# ECG.net
KiCad netlist of a schematic drawn in EAGLE
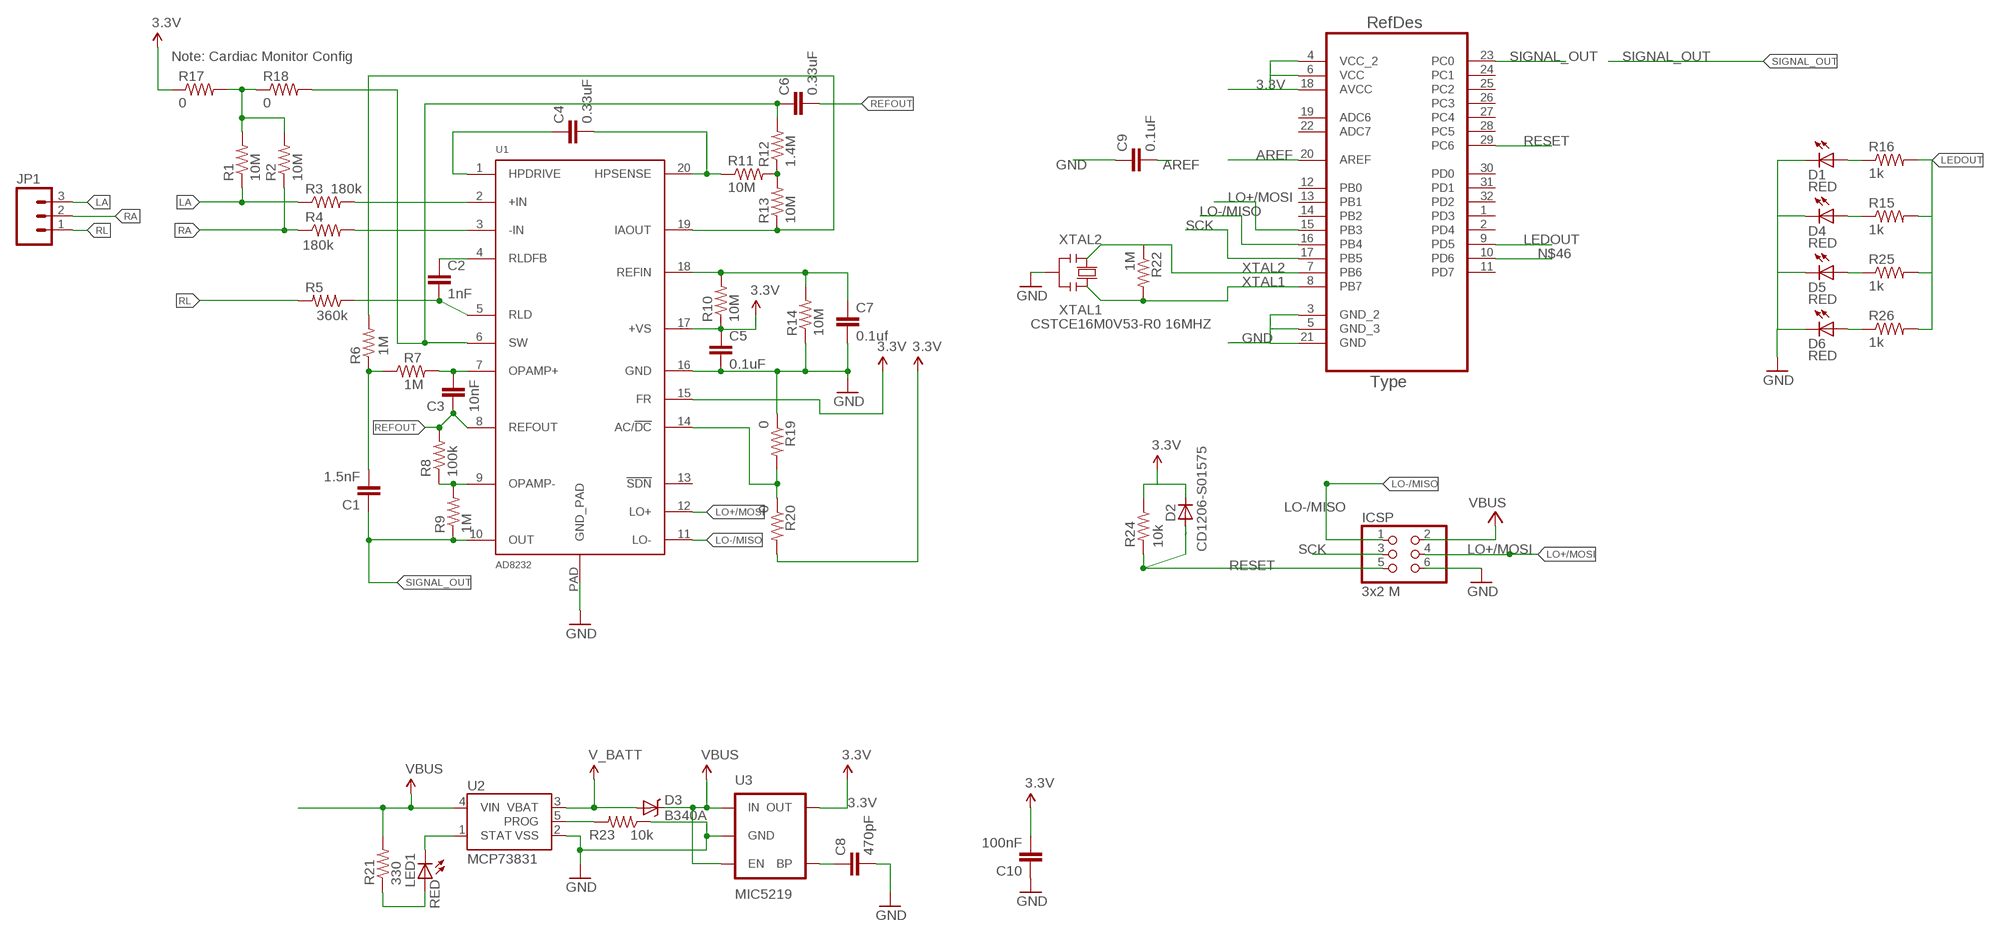
[diagram p0: schematic, sheet 1]

(export (version "E")
  (design (tool "Eeschema 10.0.6"))
  (components
    (comp (ref "C1")
      (value "1.5nF")
      (footprint "eagle-import:0402-CAP")
      (libsource (lib "eagle-import") (part "CAP0402-CAP"))
    )
    (comp (ref "C2")
      (value "1nF")
      (footprint "eagle-import:0402-CAP")
      (libsource (lib "eagle-import") (part "CAP0402-CAP"))
    )
    (comp (ref "C3")
      (value "10nF")
      (footprint "eagle-import:0402-CAP")
      (libsource (lib "eagle-import") (part "CAP0402-CAP"))
    )
    (comp (ref "C4")
      (value "0.33uF")
      (footprint "eagle-import:0805")
      (libsource (lib "eagle-import") (part "CAP0805"))
    )
    (comp (ref "C5")
      (value "0.1uF")
      (footprint "eagle-import:0402-CAP")
      (libsource (lib "eagle-import") (part "CAP0402-CAP"))
    )
    (comp (ref "C6")
      (value "0.33uF")
      (footprint "eagle-import:0805")
      (libsource (lib "eagle-import") (part "CAP0805"))
    )
    (comp (ref "C7")
      (value "0.1uf")
      (footprint "eagle-import:0402-CAP")
      (libsource (lib "eagle-import") (part "CAP0402-CAP"))
    )
    (comp (ref "C8")
      (value "470pF")
      (footprint "eagle-import:0603-CAP")
      (libsource (lib "eagle-import") (part "CAP0603-CAP"))
    )
    (comp (ref "C9")
      (value "0.1uF")
      (footprint "eagle-import:0402-CAP")
      (libsource (lib "eagle-import") (part "CAP0402-CAP"))
    )
    (comp (ref "C10")
      (value "100nF")
      (footprint "eagle-import:0402-CAP")
      (libsource (lib "eagle-import") (part "CAP0402-CAP"))
    )
    (comp (ref "D1")
      (value "RED")
      (footprint "eagle-import:LED-0603@1")
      (libsource (lib "eagle-import") (part "LED-RED0603"))
    )
    (comp (ref "D2")
      (value "CD1206-S01575")
      (footprint "eagle-import:MINIMELF")
      (libsource (lib "eagle-import") (part "DIODE-MINIMELF"))
    )
    (comp (ref "D3")
      (value "B340A")
      (footprint "eagle-import:SMA-DIODE")
      (libsource (lib "eagle-import") (part "DIODE-SCHOTTKY-B340A"))
    )
    (comp (ref "D4")
      (value "RED")
      (footprint "eagle-import:LED-0603@1")
      (libsource (lib "eagle-import") (part "LED-RED0603"))
    )
    (comp (ref "D5")
      (value "RED")
      (footprint "eagle-import:LED-0603@1")
      (libsource (lib "eagle-import") (part "LED-RED0603"))
    )
    (comp (ref "D6")
      (value "RED")
      (footprint "eagle-import:LED-0603@1")
      (libsource (lib "eagle-import") (part "LED-RED0603"))
    )
    (comp (ref "ICSP")
      (value "3x2 M")
      (footprint "eagle-import:2X03")
      (libsource (lib "eagle-import") (part "PINHD-2X3"))
    )
    (comp (ref "JP1")
      (value "M03PTH")
      (footprint "eagle-import:1X03")
      (libsource (lib "eagle-import") (part "M03PTH"))
    )
    (comp (ref "LED1")
      (value "RED")
      (footprint "eagle-import:LED-0603")
      (libsource (lib "eagle-import") (part "LED0603"))
    )
    (comp (ref "R1")
      (value "10M")
      (footprint "eagle-import:0402-RES")
      (libsource (lib "eagle-import") (part "RESISTOR0402-RES"))
    )
    (comp (ref "R2")
      (value "10M")
      (footprint "eagle-import:0402-RES")
      (libsource (lib "eagle-import") (part "RESISTOR0402-RES"))
    )
    (comp (ref "R3")
      (value "180k")
      (footprint "eagle-import:0402-RES")
      (libsource (lib "eagle-import") (part "RESISTOR0402-RES"))
    )
    (comp (ref "R4")
      (value "180k")
      (footprint "eagle-import:0402-RES")
      (libsource (lib "eagle-import") (part "RESISTOR0402-RES"))
    )
    (comp (ref "R5")
      (value "360k")
      (footprint "eagle-import:0402-RES")
      (libsource (lib "eagle-import") (part "RESISTOR0402-RES"))
    )
    (comp (ref "R6")
      (value "1M")
      (footprint "eagle-import:0402-RES")
      (libsource (lib "eagle-import") (part "RESISTOR0402-RES"))
    )
    (comp (ref "R7")
      (value "1M")
      (footprint "eagle-import:0402-RES")
      (libsource (lib "eagle-import") (part "RESISTOR0402-RES"))
    )
    (comp (ref "R8")
      (value "100k")
      (footprint "eagle-import:0402-RES")
      (libsource (lib "eagle-import") (part "RESISTOR0402-RES"))
    )
    (comp (ref "R9")
      (value "1M")
      (footprint "eagle-import:0402-RES")
      (libsource (lib "eagle-import") (part "RESISTOR0402-RES"))
    )
    (comp (ref "R10")
      (value "10M")
      (footprint "eagle-import:0402-RES")
      (libsource (lib "eagle-import") (part "RESISTOR0402-RES"))
    )
    (comp (ref "R11")
      (value "10M")
      (footprint "eagle-import:0402-RES")
      (libsource (lib "eagle-import") (part "RESISTOR0402-RES"))
    )
    (comp (ref "R12")
      (value "1.4M")
      (footprint "eagle-import:0402-RES")
      (libsource (lib "eagle-import") (part "RESISTOR0402-RES"))
    )
    (comp (ref "R13")
      (value "10M")
      (footprint "eagle-import:0402-RES")
      (libsource (lib "eagle-import") (part "RESISTOR0402-RES"))
    )
    (comp (ref "R14")
      (value "10M")
      (footprint "eagle-import:0402-RES")
      (libsource (lib "eagle-import") (part "RESISTOR0402-RES"))
    )
    (comp (ref "R15")
      (value "1k")
      (footprint "eagle-import:0603-RES@1")
      (libsource (lib "eagle-import") (part "1K-1%"))
    )
    (comp (ref "R16")
      (value "1k")
      (footprint "eagle-import:0603-RES@1")
      (libsource (lib "eagle-import") (part "1K-1%"))
    )
    (comp (ref "R17")
      (value "0")
      (footprint "eagle-import:0603")
      (libsource (lib "eagle-import") (part "0OHM1/10W5%(0603)"))
    )
    (comp (ref "R18")
      (value "0")
      (footprint "eagle-import:0603")
      (libsource (lib "eagle-import") (part "0OHM1/10W5%(0603)"))
    )
    (comp (ref "R19")
      (value "0")
      (footprint "eagle-import:0603")
      (libsource (lib "eagle-import") (part "0OHM1/10W5%(0603)"))
    )
    (comp (ref "R20")
      (value "0")
      (footprint "eagle-import:0603")
      (libsource (lib "eagle-import") (part "0OHM1/10W5%(0603)"))
    )
    (comp (ref "R21")
      (value "330")
      (footprint "eagle-import:0603-RES")
      (libsource (lib "eagle-import") (part "RESISTOR0603-RES"))
    )
    (comp (ref "R22")
      (value "1M")
      (footprint "eagle-import:0402-RES")
      (libsource (lib "eagle-import") (part "RESISTOR0402-RES"))
    )
    (comp (ref "R23")
      (value "10k")
      (footprint "eagle-import:0603-RES")
      (libsource (lib "eagle-import") (part "SparkFun-Resistors_RESISTOR0603-RES"))
    )
    (comp (ref "R24")
      (value "10k")
      (footprint "eagle-import:0402-RES")
      (libsource (lib "eagle-import") (part "RESISTOR0402-RES"))
    )
    (comp (ref "R25")
      (value "1k")
      (footprint "eagle-import:0603-RES@1")
      (libsource (lib "eagle-import") (part "1K-1%"))
    )
    (comp (ref "R26")
      (value "1k")
      (footprint "eagle-import:0603-RES@1")
      (libsource (lib "eagle-import") (part "1K-1%"))
    )
    (comp (ref "U1")
      (value "AD8232")
      (footprint "eagle-import:LFCSP_20")
      (libsource (lib "eagle-import") (part "AD8232"))
    )
    (comp (ref "U2")
      (value "MCP73831")
      (footprint "eagle-import:SOT23-5")
      (fields (field (name "PROD_ID") "IC-09995"))
      (libsource (lib "eagle-import") (part "MCP73831"))
    )
    (comp (ref "U3")
      (value "MIC5219")
      (footprint "eagle-import:SOT23-5")
      (fields (field (name "PROD_ID") "VREG-09872"))
      (libsource (lib "eagle-import") (part "V_REG_MIC52193.3V"))
    )
    (comp (ref "U4")
      (value "ATMEGA328P-AU")
      (footprint "eagle-import:QFP80P900X900X120-32N")
      (libsource (lib "eagle-import") (part "ATMEGA328P-AU"))
    )
    (comp (ref "Y2")
      (value "CSTCE16M0V53-R0 16MHZ")
      (footprint "eagle-import:RESONATOR")
      (libsource (lib "eagle-import") (part "RESONATORMU"))
    )
  )
  (nets
    (net (code "1") (name "/AREF") (class "Default")
      (node (ref "C9") (pin "2") (pinfunction "2_2") (pintype "passive"))
      (node (ref "U4") (pin "20") (pinfunction "AREF_20") (pintype "input"))
    )
    (net (code "2") (name "/N$46") (class "Default")
      (node (ref "U4") (pin "10") (pinfunction "PD6_10") (pintype "bidirectional"))
    )
    (net (code "3") (name "/RESET") (class "Default")
      (node (ref "D2") (pin "A") (pinfunction "A_A") (pintype "passive"))
      (node (ref "ICSP") (pin "5") (pinfunction "5_5") (pintype "passive"))
      (node (ref "R24") (pin "2") (pinfunction "2_2") (pintype "passive"))
      (node (ref "U4") (pin "29") (pinfunction "PC6_29") (pintype "bidirectional"))
    )
    (net (code "4") (name "/SCK") (class "Default")
      (node (ref "ICSP") (pin "3") (pinfunction "3_3") (pintype "passive"))
      (node (ref "U4") (pin "17") (pinfunction "PB5_17") (pintype "bidirectional"))
    )
    (net (code "5") (name "/XTAL1") (class "Default")
      (node (ref "R22") (pin "2") (pinfunction "2_2") (pintype "passive"))
      (node (ref "U4") (pin "8") (pinfunction "PB7_8") (pintype "bidirectional"))
      (node (ref "Y2") (pin "3") (pinfunction "3_3") (pintype "passive"))
    )
    (net (code "6") (name "/XTAL2") (class "Default")
      (node (ref "R22") (pin "1") (pinfunction "1_1") (pintype "passive"))
      (node (ref "U4") (pin "7") (pinfunction "PB6_7") (pintype "bidirectional"))
      (node (ref "Y2") (pin "1") (pinfunction "1_1") (pintype "passive"))
    )
    (net (code "7") (name "3.3V") (class "Default")
      (node (ref "C10") (pin "2") (pinfunction "2_2") (pintype "passive"))
      (node (ref "C5") (pin "1") (pinfunction "1_1") (pintype "passive"))
      (node (ref "D2") (pin "C") (pinfunction "C_C") (pintype "passive"))
      (node (ref "R10") (pin "1") (pinfunction "1_1") (pintype "passive"))
      (node (ref "R17") (pin "1") (pinfunction "1_1") (pintype "passive"))
      (node (ref "R20") (pin "2") (pinfunction "2_2") (pintype "passive"))
      (node (ref "R24") (pin "1") (pinfunction "1_1") (pintype "passive"))
      (node (ref "U1") (pin "15") (pinfunction "FR_15") (pintype "bidirectional"))
      (node (ref "U1") (pin "17") (pinfunction "+VS_17") (pintype "bidirectional"))
      (node (ref "U3") (pin "5") (pinfunction "OUT_5") (pintype "passive"))
      (node (ref "U4") (pin "18") (pinfunction "AVCC_18") (pintype "power_in"))
      (node (ref "U4") (pin "4") (pinfunction "VCC_2_4") (pintype "power_in"))
      (node (ref "U4") (pin "6") (pinfunction "VCC_6") (pintype "power_in"))
    )
    (net (code "8") (name "GND") (class "Default")
      (node (ref "C10") (pin "1") (pinfunction "1_1") (pintype "passive"))
      (node (ref "C5") (pin "2") (pinfunction "2_2") (pintype "passive"))
      (node (ref "C7") (pin "2") (pinfunction "2_2") (pintype "passive"))
      (node (ref "C8") (pin "2") (pinfunction "2_2") (pintype "passive"))
      (node (ref "C9") (pin "1") (pinfunction "1_1") (pintype "passive"))
      (node (ref "D1") (pin "C") (pinfunction "C_C") (pintype "passive"))
      (node (ref "D4") (pin "C") (pinfunction "C_C") (pintype "passive"))
      (node (ref "D5") (pin "C") (pinfunction "C_C") (pintype "passive"))
      (node (ref "D6") (pin "C") (pinfunction "C_C") (pintype "passive"))
      (node (ref "ICSP") (pin "6") (pinfunction "6_6") (pintype "passive"))
      (node (ref "R14") (pin "1") (pinfunction "1_1") (pintype "passive"))
      (node (ref "R19") (pin "1") (pinfunction "1_1") (pintype "passive"))
      (node (ref "R23") (pin "1") (pinfunction "1_1") (pintype "passive"))
      (node (ref "U1") (pin "16") (pinfunction "GND_16") (pintype "bidirectional"))
      (node (ref "U1") (pin "PAD") (pinfunction "GND_PAD_PAD") (pintype "bidirectional"))
      (node (ref "U2") (pin "2") (pinfunction "VSS_2") (pintype "power_in"))
      (node (ref "U3") (pin "2") (pinfunction "GND_2") (pintype "input"))
      (node (ref "U4") (pin "21") (pinfunction "GND_21") (pintype "passive"))
      (node (ref "U4") (pin "3") (pinfunction "GND_2_3") (pintype "passive"))
      (node (ref "U4") (pin "5") (pinfunction "GND_3_5") (pintype "passive"))
      (node (ref "Y2") (pin "2") (pinfunction "2_2") (pintype "passive"))
    )
    (net (code "9") (name "LA") (class "Default")
      (node (ref "JP1") (pin "3") (pinfunction "3_3") (pintype "passive"))
      (node (ref "R1") (pin "1") (pinfunction "1_1") (pintype "passive"))
      (node (ref "R3") (pin "1") (pinfunction "1_1") (pintype "passive"))
    )
    (net (code "10") (name "LEDOUT") (class "Default")
      (node (ref "R15") (pin "2") (pinfunction "2_2") (pintype "passive"))
      (node (ref "R16") (pin "2") (pinfunction "2_2") (pintype "passive"))
      (node (ref "R25") (pin "2") (pinfunction "2_2") (pintype "passive"))
      (node (ref "R26") (pin "2") (pinfunction "2_2") (pintype "passive"))
      (node (ref "U4") (pin "9") (pinfunction "PD5_9") (pintype "bidirectional"))
    )
    (net (code "11") (name "LO+{slash}MOSI") (class "Default")
      (node (ref "ICSP") (pin "4") (pinfunction "4_4") (pintype "passive"))
      (node (ref "U1") (pin "12") (pinfunction "LO+_12") (pintype "bidirectional"))
      (node (ref "U4") (pin "15") (pinfunction "PB3_15") (pintype "bidirectional"))
    )
    (net (code "12") (name "LO-{slash}MISO") (class "Default")
      (node (ref "ICSP") (pin "1") (pinfunction "1_1") (pintype "passive"))
      (node (ref "U1") (pin "11") (pinfunction "LO-_11") (pintype "bidirectional"))
      (node (ref "U4") (pin "16") (pinfunction "PB4_16") (pintype "bidirectional"))
    )
    (net (code "13") (name "Net-(C1-Pad2)") (class "Default")
      (node (ref "C1") (pin "2") (pinfunction "2_2") (pintype "passive"))
      (node (ref "R6") (pin "1") (pinfunction "1_1") (pintype "passive"))
      (node (ref "R7") (pin "1") (pinfunction "1_1") (pintype "passive"))
    )
    (net (code "14") (name "Net-(D1-PadA)") (class "Default")
      (node (ref "D1") (pin "A") (pinfunction "A_A") (pintype "passive"))
      (node (ref "R16") (pin "1") (pinfunction "1_1") (pintype "passive"))
    )
    (net (code "15") (name "Net-(D4-PadA)") (class "Default")
      (node (ref "D4") (pin "A") (pinfunction "A_A") (pintype "passive"))
      (node (ref "R15") (pin "1") (pinfunction "1_1") (pintype "passive"))
    )
    (net (code "16") (name "Net-(D5-PadA)") (class "Default")
      (node (ref "D5") (pin "A") (pinfunction "A_A") (pintype "passive"))
      (node (ref "R25") (pin "1") (pinfunction "1_1") (pintype "passive"))
    )
    (net (code "17") (name "Net-(D6-PadA)") (class "Default")
      (node (ref "D6") (pin "A") (pinfunction "A_A") (pintype "passive"))
      (node (ref "R26") (pin "1") (pinfunction "1_1") (pintype "passive"))
    )
    (net (code "18") (name "Net-(LED1-PadA)") (class "Default")
      (node (ref "LED1") (pin "A") (pinfunction "A_A") (pintype "passive"))
      (node (ref "R21") (pin "1") (pinfunction "1_1") (pintype "passive"))
    )
    (net (code "19") (name "Net-(R1-Pad2)") (class "Default")
      (node (ref "R1") (pin "2") (pinfunction "2_2") (pintype "passive"))
      (node (ref "R17") (pin "2") (pinfunction "2_2") (pintype "passive"))
      (node (ref "R18") (pin "1") (pinfunction "1_1") (pintype "passive"))
      (node (ref "R2") (pin "2") (pinfunction "2_2") (pintype "passive"))
    )
    (net (code "20") (name "Net-(R11-Pad2)") (class "Default")
      (node (ref "R11") (pin "2") (pinfunction "2_2") (pintype "passive"))
      (node (ref "R12") (pin "1") (pinfunction "1_1") (pintype "passive"))
      (node (ref "R13") (pin "2") (pinfunction "2_2") (pintype "passive"))
    )
    (net (code "21") (name "Net-(U1-+IN)") (class "Default")
      (node (ref "R3") (pin "2") (pinfunction "2_2") (pintype "passive"))
      (node (ref "U1") (pin "2") (pinfunction "+IN_2") (pintype "bidirectional"))
    )
    (net (code "22") (name "Net-(U1--IN)") (class "Default")
      (node (ref "R4") (pin "2") (pinfunction "2_2") (pintype "passive"))
      (node (ref "U1") (pin "3") (pinfunction "-IN_3") (pintype "bidirectional"))
    )
    (net (code "23") (name "Net-(U1-AC{slash}~{DC})") (class "Default")
      (node (ref "R19") (pin "2") (pinfunction "2_2") (pintype "passive"))
      (node (ref "R20") (pin "1") (pinfunction "1_1") (pintype "passive"))
      (node (ref "U1") (pin "14") (pinfunction "AC/~{DC}_14") (pintype "bidirectional"))
    )
    (net (code "24") (name "Net-(U1-HPDRIVE)") (class "Default")
      (node (ref "C4") (pin "1") (pinfunction "1_1") (pintype "passive"))
      (node (ref "U1") (pin "1") (pinfunction "HPDRIVE_1") (pintype "bidirectional"))
    )
    (net (code "25") (name "Net-(U1-HPSENSE)") (class "Default")
      (node (ref "C4") (pin "2") (pinfunction "2_2") (pintype "passive"))
      (node (ref "R11") (pin "1") (pinfunction "1_1") (pintype "passive"))
      (node (ref "U1") (pin "20") (pinfunction "HPSENSE_20") (pintype "bidirectional"))
    )
    (net (code "26") (name "Net-(U1-IAOUT)") (class "Default")
      (node (ref "R13") (pin "1") (pinfunction "1_1") (pintype "passive"))
      (node (ref "R6") (pin "2") (pinfunction "2_2") (pintype "passive"))
      (node (ref "U1") (pin "19") (pinfunction "IAOUT_19") (pintype "bidirectional"))
    )
    (net (code "27") (name "Net-(U1-OPAMP+)") (class "Default")
      (node (ref "C3") (pin "2") (pinfunction "2_2") (pintype "passive"))
      (node (ref "R7") (pin "2") (pinfunction "2_2") (pintype "passive"))
      (node (ref "U1") (pin "7") (pinfunction "OPAMP+_7") (pintype "bidirectional"))
    )
    (net (code "28") (name "Net-(U1-OPAMP-)") (class "Default")
      (node (ref "R8") (pin "1") (pinfunction "1_1") (pintype "passive"))
      (node (ref "R9") (pin "2") (pinfunction "2_2") (pintype "passive"))
      (node (ref "U1") (pin "9") (pinfunction "OPAMP-_9") (pintype "bidirectional"))
    )
    (net (code "29") (name "Net-(U1-REFIN)") (class "Default")
      (node (ref "C7") (pin "1") (pinfunction "1_1") (pintype "passive"))
      (node (ref "R10") (pin "2") (pinfunction "2_2") (pintype "passive"))
      (node (ref "R14") (pin "2") (pinfunction "2_2") (pintype "passive"))
      (node (ref "U1") (pin "18") (pinfunction "REFIN_18") (pintype "bidirectional"))
    )
    (net (code "30") (name "Net-(U1-RLD)") (class "Default")
      (node (ref "C2") (pin "2") (pinfunction "2_2") (pintype "passive"))
      (node (ref "R5") (pin "1") (pinfunction "1_1") (pintype "passive"))
      (node (ref "U1") (pin "5") (pinfunction "RLD_5") (pintype "bidirectional"))
    )
    (net (code "31") (name "Net-(U1-RLDFB)") (class "Default")
      (node (ref "C2") (pin "1") (pinfunction "1_1") (pintype "passive"))
      (node (ref "U1") (pin "4") (pinfunction "RLDFB_4") (pintype "bidirectional"))
    )
    (net (code "32") (name "Net-(U1-SW)") (class "Default")
      (node (ref "C6") (pin "1") (pinfunction "1_1") (pintype "passive"))
      (node (ref "R12") (pin "2") (pinfunction "2_2") (pintype "passive"))
      (node (ref "R18") (pin "2") (pinfunction "2_2") (pintype "passive"))
      (node (ref "U1") (pin "6") (pinfunction "SW_6") (pintype "bidirectional"))
    )
    (net (code "33") (name "Net-(U2-PROG)") (class "Default")
      (node (ref "R23") (pin "2") (pinfunction "2_2") (pintype "passive"))
      (node (ref "U2") (pin "5") (pinfunction "PROG_5") (pintype "input"))
    )
    (net (code "34") (name "Net-(U2-STAT)") (class "Default")
      (node (ref "LED1") (pin "C") (pinfunction "C_C") (pintype "passive"))
      (node (ref "U2") (pin "1") (pinfunction "STAT_1") (pintype "output"))
    )
    (net (code "35") (name "Net-(U3-BP)") (class "Default")
      (node (ref "C8") (pin "1") (pinfunction "1_1") (pintype "passive"))
      (node (ref "U3") (pin "4") (pinfunction "BP_4") (pintype "input"))
    )
    (net (code "36") (name "RA") (class "Default")
      (node (ref "JP1") (pin "2") (pinfunction "2_2") (pintype "passive"))
      (node (ref "R2") (pin "1") (pinfunction "1_1") (pintype "passive"))
      (node (ref "R4") (pin "1") (pinfunction "1_1") (pintype "passive"))
    )
    (net (code "37") (name "REFOUT") (class "Default")
      (node (ref "C3") (pin "1") (pinfunction "1_1") (pintype "passive"))
      (node (ref "C6") (pin "2") (pinfunction "2_2") (pintype "passive"))
      (node (ref "R8") (pin "2") (pinfunction "2_2") (pintype "passive"))
      (node (ref "U1") (pin "8") (pinfunction "REFOUT_8") (pintype "bidirectional"))
    )
    (net (code "38") (name "RL") (class "Default")
      (node (ref "JP1") (pin "1") (pinfunction "1_1") (pintype "passive"))
      (node (ref "R5") (pin "2") (pinfunction "2_2") (pintype "passive"))
    )
    (net (code "39") (name "SIGNAL_OUT") (class "Default")
      (node (ref "C1") (pin "1") (pinfunction "1_1") (pintype "passive"))
      (node (ref "R9") (pin "1") (pinfunction "1_1") (pintype "passive"))
      (node (ref "U1") (pin "10") (pinfunction "OUT_10") (pintype "bidirectional"))
      (node (ref "U4") (pin "23") (pinfunction "PC0_23") (pintype "bidirectional"))
    )
    (net (code "40") (name "VBUS") (class "Default")
      (node (ref "D3") (pin "C") (pinfunction "C_C") (pintype "passive"))
      (node (ref "ICSP") (pin "2") (pinfunction "2_2") (pintype "passive"))
      (node (ref "R21") (pin "2") (pinfunction "2_2") (pintype "passive"))
      (node (ref "U2") (pin "4") (pinfunction "VIN_4") (pintype "power_in"))
      (node (ref "U3") (pin "1") (pinfunction "IN_1") (pintype "input"))
      (node (ref "U3") (pin "3") (pinfunction "EN_3") (pintype "input"))
    )
    (net (code "41") (name "V_BATT") (class "Default")
      (node (ref "D3") (pin "A") (pinfunction "A_A") (pintype "passive"))
      (node (ref "U2") (pin "3") (pinfunction "VBAT_3") (pintype "power_in"))
    )
    (net (code "42") (name "unconnected-(U1-~{SDN}-Pad13)") (class "Default")
      (node (ref "U1") (pin "13") (pinfunction "~{SDN}_13") (pintype "bidirectional"))
    )
    (net (code "43") (name "unconnected-(U4-ADC6-Pad19)") (class "Default")
      (node (ref "U4") (pin "19") (pinfunction "ADC6_19") (pintype "input"))
    )
    (net (code "44") (name "unconnected-(U4-ADC7-Pad22)") (class "Default")
      (node (ref "U4") (pin "22") (pinfunction "ADC7_22") (pintype "input"))
    )
    (net (code "45") (name "unconnected-(U4-PB0-Pad12)") (class "Default")
      (node (ref "U4") (pin "12") (pinfunction "PB0_12") (pintype "bidirectional"))
    )
    (net (code "46") (name "unconnected-(U4-PB1-Pad13)") (class "Default")
      (node (ref "U4") (pin "13") (pinfunction "PB1_13") (pintype "bidirectional"))
    )
    (net (code "47") (name "unconnected-(U4-PB2-Pad14)") (class "Default")
      (node (ref "U4") (pin "14") (pinfunction "PB2_14") (pintype "bidirectional"))
    )
    (net (code "48") (name "unconnected-(U4-PC1-Pad24)") (class "Default")
      (node (ref "U4") (pin "24") (pinfunction "PC1_24") (pintype "bidirectional"))
    )
    (net (code "49") (name "unconnected-(U4-PC2-Pad25)") (class "Default")
      (node (ref "U4") (pin "25") (pinfunction "PC2_25") (pintype "bidirectional"))
    )
    (net (code "50") (name "unconnected-(U4-PC3-Pad26)") (class "Default")
      (node (ref "U4") (pin "26") (pinfunction "PC3_26") (pintype "bidirectional"))
    )
    (net (code "51") (name "unconnected-(U4-PC4-Pad27)") (class "Default")
      (node (ref "U4") (pin "27") (pinfunction "PC4_27") (pintype "bidirectional"))
    )
    (net (code "52") (name "unconnected-(U4-PC5-Pad28)") (class "Default")
      (node (ref "U4") (pin "28") (pinfunction "PC5_28") (pintype "bidirectional"))
    )
    (net (code "53") (name "unconnected-(U4-PD0-Pad30)") (class "Default")
      (node (ref "U4") (pin "30") (pinfunction "PD0_30") (pintype "bidirectional"))
    )
    (net (code "54") (name "unconnected-(U4-PD1-Pad31)") (class "Default")
      (node (ref "U4") (pin "31") (pinfunction "PD1_31") (pintype "bidirectional"))
    )
    (net (code "55") (name "unconnected-(U4-PD2-Pad32)") (class "Default")
      (node (ref "U4") (pin "32") (pinfunction "PD2_32") (pintype "bidirectional"))
    )
    (net (code "56") (name "unconnected-(U4-PD3-Pad1)") (class "Default")
      (node (ref "U4") (pin "1") (pinfunction "PD3_1") (pintype "bidirectional"))
    )
    (net (code "57") (name "unconnected-(U4-PD4-Pad2)") (class "Default")
      (node (ref "U4") (pin "2") (pinfunction "PD4_2") (pintype "bidirectional"))
    )
    (net (code "58") (name "unconnected-(U4-PD7-Pad11)") (class "Default")
      (node (ref "U4") (pin "11") (pinfunction "PD7_11") (pintype "bidirectional"))
    )
  )
)
